# Regulator.net
KiCad netlist of a schematic drawn in Altium Designer
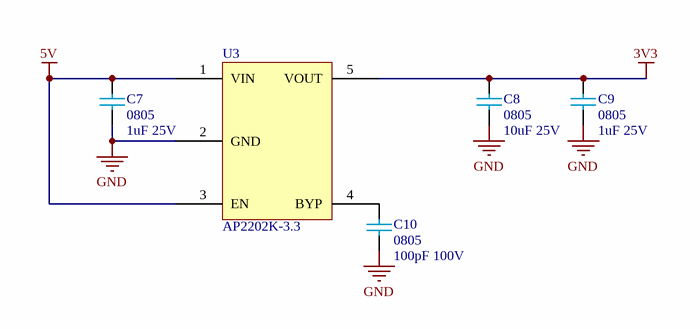
[diagram p0: Regulator.SchDoc]

(export (version "E")
  (design (tool "Eeschema 10.0.6"))
  (components
    (comp (ref "C7")
      (value "0805")
      (footprint "0805")
      (description "0805, X5R or better")
      (fields (field (name "ALTIUM_VALUE") "1uF 25V"))
      (libsource (lib "Chip_Passives") (part "Cap 1uF 25V"))
    )
    (comp (ref "C8")
      (value "0805")
      (footprint "0805")
      (description "0805, X5R or better")
      (fields (field (name "ALTIUM_VALUE") "10uF 25V"))
      (libsource (lib "Chip_Passives") (part "Cap 10uF 25V"))
    )
    (comp (ref "C9")
      (value "0805")
      (footprint "0805")
      (description "0805, X5R or better")
      (fields (field (name "ALTIUM_VALUE") "1uF 25V"))
      (libsource (lib "Chip_Passives") (part "Cap 1uF 25V"))
    )
    (comp (ref "C10")
      (value "0805")
      (footprint "0805")
      (description "0805, X5R or better")
      (fields (field (name "ALTIUM_VALUE") "100pF 100V"))
      (libsource (lib "Chip_Passives") (part "Cap 100pF 100V"))
    )
    (comp (ref "U3")
      (value "AP2202K-3.3")
      (footprint "AP2202 - SOT95P270X145-5N")
      (description "3.3V 150mA LDO regulator")
      (libsource (lib "PowerSupply") (part "AP2202K-3.3"))
    )
  )
  (nets
    (net (code "1") (name "3V3") (class "Default")
      (node (ref "C8") (pin "2") (pinfunction "2_2") (pintype "passive"))
      (node (ref "C9") (pin "2") (pinfunction "2_2") (pintype "passive"))
      (node (ref "U3") (pin "5") (pinfunction "VOUT_5") (pintype "passive"))
    )
    (net (code "2") (name "5V") (class "Default")
      (node (ref "C7") (pin "2") (pinfunction "2_2") (pintype "passive"))
      (node (ref "U3") (pin "1") (pinfunction "VIN_1") (pintype "passive"))
      (node (ref "U3") (pin "3") (pinfunction "EN_3") (pintype "passive"))
    )
    (net (code "3") (name "GND") (class "Default")
      (node (ref "C10") (pin "1") (pinfunction "1_1") (pintype "passive"))
      (node (ref "C7") (pin "1") (pinfunction "1_1") (pintype "passive"))
      (node (ref "C8") (pin "1") (pinfunction "1_1") (pintype "passive"))
      (node (ref "C9") (pin "1") (pinfunction "1_1") (pintype "passive"))
      (node (ref "U3") (pin "2") (pinfunction "GND_2") (pintype "passive"))
    )
    (net (code "4") (name "Net-(U3-BYP)") (class "Default")
      (node (ref "C10") (pin "2") (pinfunction "2_2") (pintype "passive"))
      (node (ref "U3") (pin "4") (pinfunction "BYP_4") (pintype "passive"))
    )
  )
)
